# Rain_alarm.net
KiCad netlist of a schematic drawn in EAGLE
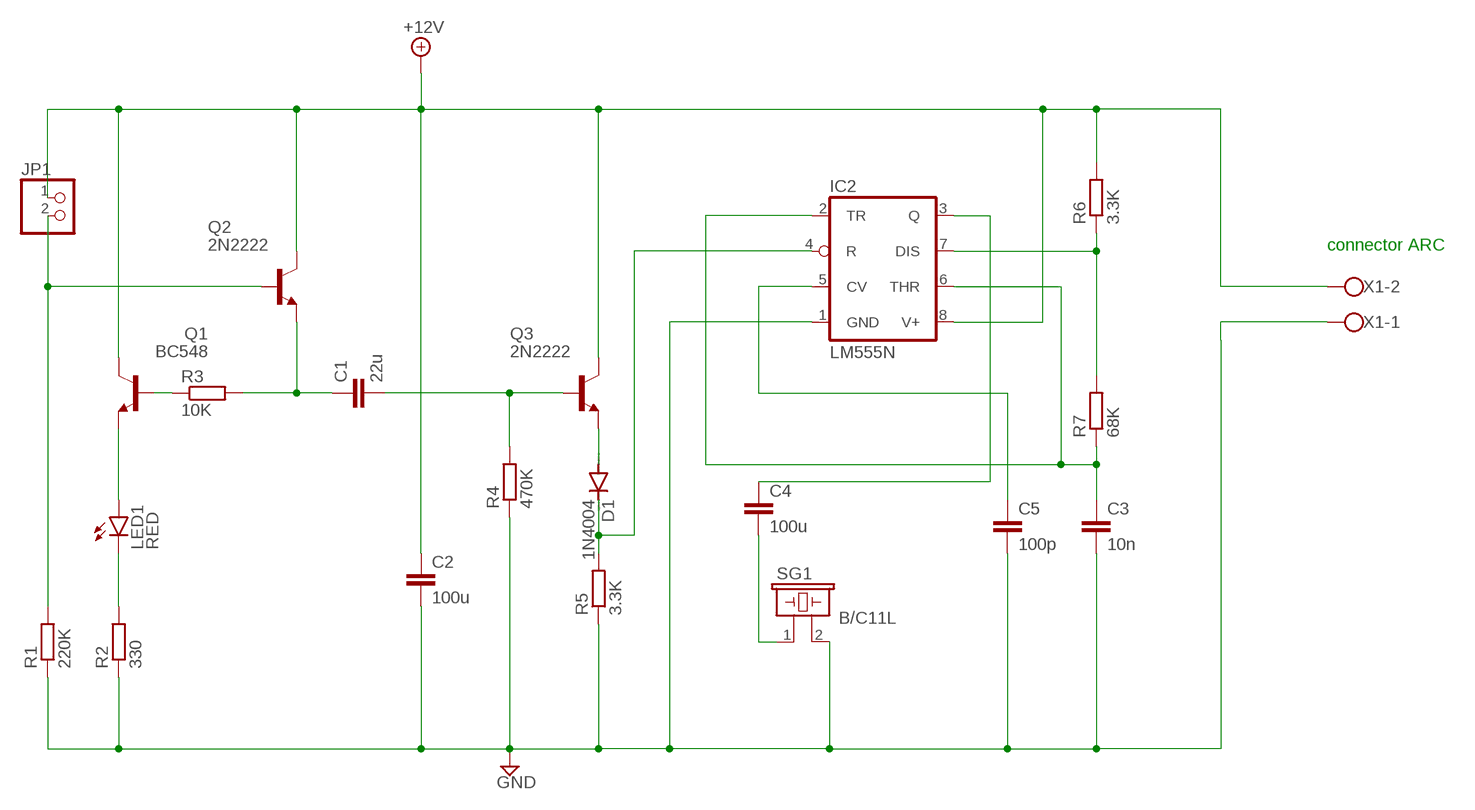
[diagram p0: schematic, sheet 1]

(export (version "E")
  (design (tool "Eeschema 10.0.6"))
  (components
    (comp (ref "C1")
      (value "22u")
      (footprint "eagle-import:C025-025X050")
      (libsource (lib "eagle-import") (part "C-EU025-025X050"))
    )
    (comp (ref "C2")
      (value "100u")
      (footprint "eagle-import:C025-025X050")
      (libsource (lib "eagle-import") (part "C-EU025-025X050"))
    )
    (comp (ref "C3")
      (value "10n")
      (footprint "eagle-import:C025-025X050")
      (libsource (lib "eagle-import") (part "C-EU025-025X050"))
    )
    (comp (ref "C4")
      (value "100u")
      (footprint "eagle-import:C025-025X050")
      (libsource (lib "eagle-import") (part "C-EU025-025X050"))
    )
    (comp (ref "C5")
      (value "100p")
      (footprint "eagle-import:C025-025X050")
      (libsource (lib "eagle-import") (part "C-EU025-025X050"))
    )
    (comp (ref "D1")
      (value "1N4004")
      (footprint "eagle-import:DO41-10")
      (libsource (lib "eagle-import") (part "1N4004"))
    )
    (comp (ref "IC2")
      (value "LM555N")
      (footprint "eagle-import:DIL08")
      (libsource (lib "eagle-import") (part "555NLM"))
    )
    (comp (ref "JP1")
      (value "PINHD-1X2")
      (footprint "eagle-import:1X02")
      (libsource (lib "eagle-import") (part "PINHD-1X2"))
    )
    (comp (ref "LED1")
      (value "RED")
      (footprint "eagle-import:LED3MM")
      (libsource (lib "eagle-import") (part "LED3MM"))
    )
    (comp (ref "Q1")
      (value "BC548")
      (footprint "eagle-import:TO92-EBC")
      (libsource (lib "eagle-import") (part "BC548"))
    )
    (comp (ref "Q2")
      (value "2N2222")
      (footprint "eagle-import:TO18")
      (libsource (lib "eagle-import") (part "2N2222"))
    )
    (comp (ref "Q3")
      (value "2N2222")
      (footprint "eagle-import:TO18")
      (libsource (lib "eagle-import") (part "2N2222"))
    )
    (comp (ref "R1")
      (value "220K")
      (footprint "eagle-import:0204_7")
      (libsource (lib "eagle-import") (part "R-EU_0204/7"))
    )
    (comp (ref "R2")
      (value "330")
      (footprint "eagle-import:0204_7")
      (libsource (lib "eagle-import") (part "R-EU_0204/7"))
    )
    (comp (ref "R3")
      (value "10K")
      (footprint "eagle-import:0204_7")
      (libsource (lib "eagle-import") (part "R-EU_0204/7"))
    )
    (comp (ref "R4")
      (value "470K")
      (footprint "eagle-import:0204_7")
      (libsource (lib "eagle-import") (part "R-EU_0204/7"))
    )
    (comp (ref "R5")
      (value "3.3K")
      (footprint "eagle-import:0204_7")
      (libsource (lib "eagle-import") (part "R-EU_0204/7"))
    )
    (comp (ref "R6")
      (value "3.3K")
      (footprint "eagle-import:0204_7")
      (libsource (lib "eagle-import") (part "R-EU_0204/7"))
    )
    (comp (ref "R7")
      (value "68K")
      (footprint "eagle-import:0204_7")
      (libsource (lib "eagle-import") (part "R-EU_0204/7"))
    )
    (comp (ref "SG1")
      (value "B/C11L")
      (footprint "eagle-import:B_C11L")
      (libsource (lib "eagle-import") (part "B/C11L"))
    )
    (comp (ref "X1")
      (value "W237-102")
      (footprint "eagle-import:W237-102")
      (fields (field (name "MPN") "237-102"))
      (libsource (lib "eagle-import") (part "W237-102"))
    )
  )
  (nets
    (net (code "1") (name "+12V") (class "Default")
      (node (ref "C2") (pin "1") (pinfunction "1_1") (pintype "passive"))
      (node (ref "IC2") (pin "8") (pinfunction "V+_8") (pintype "power_in"))
      (node (ref "JP1") (pin "1") (pinfunction "1_1") (pintype "passive"))
      (node (ref "Q1") (pin "C") (pinfunction "C_C") (pintype "passive"))
      (node (ref "Q2") (pin "3") (pinfunction "C_3") (pintype "passive"))
      (node (ref "Q3") (pin "3") (pinfunction "C_3") (pintype "passive"))
      (node (ref "R6") (pin "2") (pinfunction "2_2") (pintype "passive"))
      (node (ref "X1") (pin "2") (pinfunction "KL_2") (pintype "passive"))
    )
    (net (code "2") (name "GND") (class "Default")
      (node (ref "C2") (pin "2") (pinfunction "2_2") (pintype "passive"))
      (node (ref "C3") (pin "2") (pinfunction "2_2") (pintype "passive"))
      (node (ref "C5") (pin "2") (pinfunction "2_2") (pintype "passive"))
      (node (ref "IC2") (pin "1") (pinfunction "GND_1") (pintype "power_in"))
      (node (ref "R1") (pin "1") (pinfunction "1_1") (pintype "passive"))
      (node (ref "R2") (pin "1") (pinfunction "1_1") (pintype "passive"))
      (node (ref "R4") (pin "1") (pinfunction "1_1") (pintype "passive"))
      (node (ref "R5") (pin "1") (pinfunction "1_1") (pintype "passive"))
      (node (ref "SG1") (pin "2") (pinfunction "2_2") (pintype "passive"))
      (node (ref "X1") (pin "1") (pinfunction "KL_1") (pintype "passive"))
    )
    (net (code "3") (name "Net-(C4-Pad2)") (class "Default")
      (node (ref "C4") (pin "2") (pinfunction "2_2") (pintype "passive"))
      (node (ref "SG1") (pin "1") (pinfunction "1_1") (pintype "passive"))
    )
    (net (code "4") (name "Net-(IC2-CV)") (class "Default")
      (node (ref "C5") (pin "1") (pinfunction "1_1") (pintype "passive"))
      (node (ref "IC2") (pin "5") (pinfunction "CV_5") (pintype "input"))
    )
    (net (code "5") (name "Net-(IC2-DIS)") (class "Default")
      (node (ref "IC2") (pin "7") (pinfunction "DIS_7") (pintype "input"))
      (node (ref "R6") (pin "1") (pinfunction "1_1") (pintype "passive"))
      (node (ref "R7") (pin "2") (pinfunction "2_2") (pintype "passive"))
    )
    (net (code "6") (name "Net-(IC2-Q)") (class "Default")
      (node (ref "C4") (pin "1") (pinfunction "1_1") (pintype "passive"))
      (node (ref "IC2") (pin "3") (pinfunction "Q_3") (pintype "output"))
    )
    (net (code "7") (name "Net-(IC2-R)") (class "Default")
      (node (ref "D1") (pin "C") (pinfunction "C_C") (pintype "passive"))
      (node (ref "IC2") (pin "4") (pinfunction "R_4") (pintype "input"))
      (node (ref "R5") (pin "2") (pinfunction "2_2") (pintype "passive"))
    )
    (net (code "8") (name "Net-(IC2-THR)") (class "Default")
      (node (ref "C3") (pin "1") (pinfunction "1_1") (pintype "passive"))
      (node (ref "IC2") (pin "2") (pinfunction "TR_2") (pintype "input"))
      (node (ref "IC2") (pin "6") (pinfunction "THR_6") (pintype "input"))
      (node (ref "R7") (pin "1") (pinfunction "1_1") (pintype "passive"))
    )
    (net (code "9") (name "Net-(LED1-C)") (class "Default")
      (node (ref "LED1") (pin "K") (pinfunction "C_K") (pintype "passive"))
      (node (ref "R2") (pin "2") (pinfunction "2_2") (pintype "passive"))
    )
    (net (code "10") (name "Net-(LED1-PadA)") (class "Default")
      (node (ref "LED1") (pin "A") (pinfunction "A_A") (pintype "passive"))
      (node (ref "Q1") (pin "E") (pinfunction "E_E") (pintype "passive"))
    )
    (net (code "11") (name "Net-(Q1-PadB)") (class "Default")
      (node (ref "Q1") (pin "B") (pinfunction "B_B") (pintype "passive"))
      (node (ref "R3") (pin "1") (pinfunction "1_1") (pintype "passive"))
    )
    (net (code "12") (name "Net-(Q2-B)") (class "Default")
      (node (ref "JP1") (pin "2") (pinfunction "2_2") (pintype "passive"))
      (node (ref "Q2") (pin "2") (pinfunction "B_2") (pintype "passive"))
      (node (ref "R1") (pin "2") (pinfunction "2_2") (pintype "passive"))
    )
    (net (code "13") (name "Net-(Q2-E)") (class "Default")
      (node (ref "C1") (pin "1") (pinfunction "1_1") (pintype "passive"))
      (node (ref "Q2") (pin "1") (pinfunction "E_1") (pintype "passive"))
      (node (ref "R3") (pin "2") (pinfunction "2_2") (pintype "passive"))
    )
    (net (code "14") (name "Net-(Q3-B)") (class "Default")
      (node (ref "C1") (pin "2") (pinfunction "2_2") (pintype "passive"))
      (node (ref "Q3") (pin "2") (pinfunction "B_2") (pintype "passive"))
      (node (ref "R4") (pin "2") (pinfunction "2_2") (pintype "passive"))
    )
    (net (code "15") (name "Net-(Q3-E)") (class "Default")
      (node (ref "D1") (pin "A") (pinfunction "A_A") (pintype "passive"))
      (node (ref "Q3") (pin "1") (pinfunction "E_1") (pintype "passive"))
    )
  )
)
